# LED_strips.net
KiCad netlist of a schematic drawn in Altium Designer
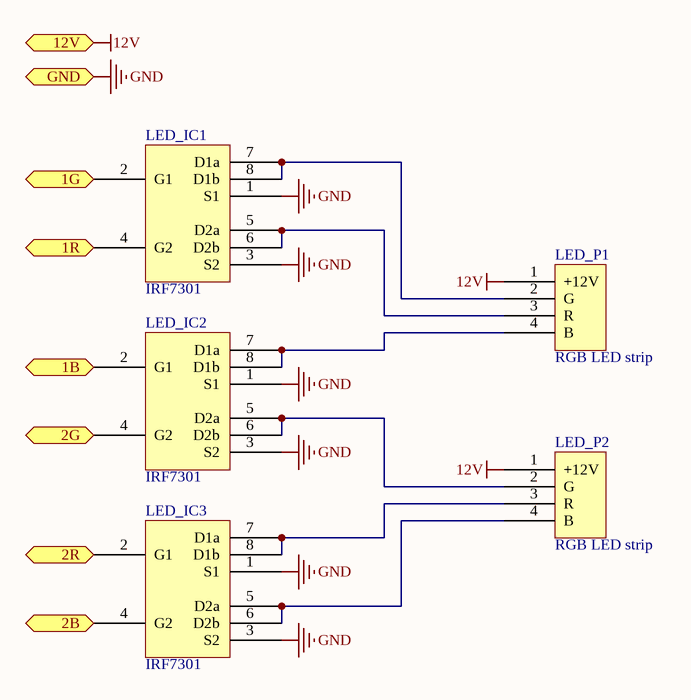
[diagram p0: LED strips.SchDoc]

(export (version "E")
  (design (tool "Eeschema 10.0.6"))
  (components
    (comp (ref "LED_IC1")
      (value "IRF7301")
      (footprint "SOIC8")
      (libsource (lib "Core51822-related") (part "IRF7301"))
    )
    (comp (ref "LED_IC2")
      (value "IRF7301")
      (footprint "SOIC8")
      (libsource (lib "Core51822-related") (part "IRF7301"))
    )
    (comp (ref "LED_IC3")
      (value "IRF7301")
      (footprint "SOIC8")
      (libsource (lib "Core51822-related") (part "IRF7301"))
    )
    (comp (ref "LED_P1") (value "RGB LED strip") (libsource (lib "Core51822-related") (part "RGB LED strip")))
    (comp (ref "LED_P2") (value "RGB LED strip") (libsource (lib "Core51822-related") (part "RGB LED strip")))
  )
  (nets
    (net (code "1") (name "/1B") (class "Default")
      (node (ref "LED_IC2") (pin "2") (pinfunction "G1_2") (pintype "passive"))
    )
    (net (code "2") (name "/1G") (class "Default")
      (node (ref "LED_IC1") (pin "2") (pinfunction "G1_2") (pintype "passive"))
    )
    (net (code "3") (name "/1R") (class "Default")
      (node (ref "LED_IC1") (pin "4") (pinfunction "G2_4") (pintype "passive"))
    )
    (net (code "4") (name "/2B") (class "Default")
      (node (ref "LED_IC3") (pin "4") (pinfunction "G2_4") (pintype "passive"))
    )
    (net (code "5") (name "/2G") (class "Default")
      (node (ref "LED_IC2") (pin "4") (pinfunction "G2_4") (pintype "passive"))
    )
    (net (code "6") (name "/2R") (class "Default")
      (node (ref "LED_IC3") (pin "2") (pinfunction "G1_2") (pintype "passive"))
    )
    (net (code "7") (name "12V") (class "Default")
      (node (ref "LED_P1") (pin "1") (pinfunction "+12V_1") (pintype "passive"))
      (node (ref "LED_P2") (pin "1") (pinfunction "+12V_1") (pintype "passive"))
    )
    (net (code "8") (name "GND") (class "Default")
      (node (ref "LED_IC1") (pin "1") (pinfunction "S1_1") (pintype "passive"))
      (node (ref "LED_IC1") (pin "3") (pinfunction "S2_3") (pintype "passive"))
      (node (ref "LED_IC2") (pin "1") (pinfunction "S1_1") (pintype "passive"))
      (node (ref "LED_IC2") (pin "3") (pinfunction "S2_3") (pintype "passive"))
      (node (ref "LED_IC3") (pin "1") (pinfunction "S1_1") (pintype "passive"))
      (node (ref "LED_IC3") (pin "3") (pinfunction "S2_3") (pintype "passive"))
    )
    (net (code "9") (name "Net-(LED_IC1-D1a)") (class "Default")
      (node (ref "LED_IC1") (pin "7") (pinfunction "D1a_7") (pintype "passive"))
      (node (ref "LED_IC1") (pin "8") (pinfunction "D1b_8") (pintype "passive"))
      (node (ref "LED_P1") (pin "2") (pinfunction "G_2") (pintype "passive"))
    )
    (net (code "10") (name "Net-(LED_IC1-D2a)") (class "Default")
      (node (ref "LED_IC1") (pin "5") (pinfunction "D2a_5") (pintype "passive"))
      (node (ref "LED_IC1") (pin "6") (pinfunction "D2b_6") (pintype "passive"))
      (node (ref "LED_P1") (pin "3") (pinfunction "R_3") (pintype "passive"))
    )
    (net (code "11") (name "Net-(LED_IC2-D1a)") (class "Default")
      (node (ref "LED_IC2") (pin "7") (pinfunction "D1a_7") (pintype "passive"))
      (node (ref "LED_IC2") (pin "8") (pinfunction "D1b_8") (pintype "passive"))
      (node (ref "LED_P1") (pin "4") (pinfunction "B_4") (pintype "passive"))
    )
    (net (code "12") (name "Net-(LED_IC2-D2a)") (class "Default")
      (node (ref "LED_IC2") (pin "5") (pinfunction "D2a_5") (pintype "passive"))
      (node (ref "LED_IC2") (pin "6") (pinfunction "D2b_6") (pintype "passive"))
      (node (ref "LED_P2") (pin "2") (pinfunction "G_2") (pintype "passive"))
    )
    (net (code "13") (name "Net-(LED_IC3-D1a)") (class "Default")
      (node (ref "LED_IC3") (pin "7") (pinfunction "D1a_7") (pintype "passive"))
      (node (ref "LED_IC3") (pin "8") (pinfunction "D1b_8") (pintype "passive"))
      (node (ref "LED_P2") (pin "3") (pinfunction "R_3") (pintype "passive"))
    )
    (net (code "14") (name "Net-(LED_IC3-D2a)") (class "Default")
      (node (ref "LED_IC3") (pin "5") (pinfunction "D2a_5") (pintype "passive"))
      (node (ref "LED_IC3") (pin "6") (pinfunction "D2b_6") (pintype "passive"))
      (node (ref "LED_P2") (pin "4") (pinfunction "B_4") (pintype "passive"))
    )
  )
)
